# cpu1_gsm.net
KiCad netlist of a schematic drawn in Altium Designer
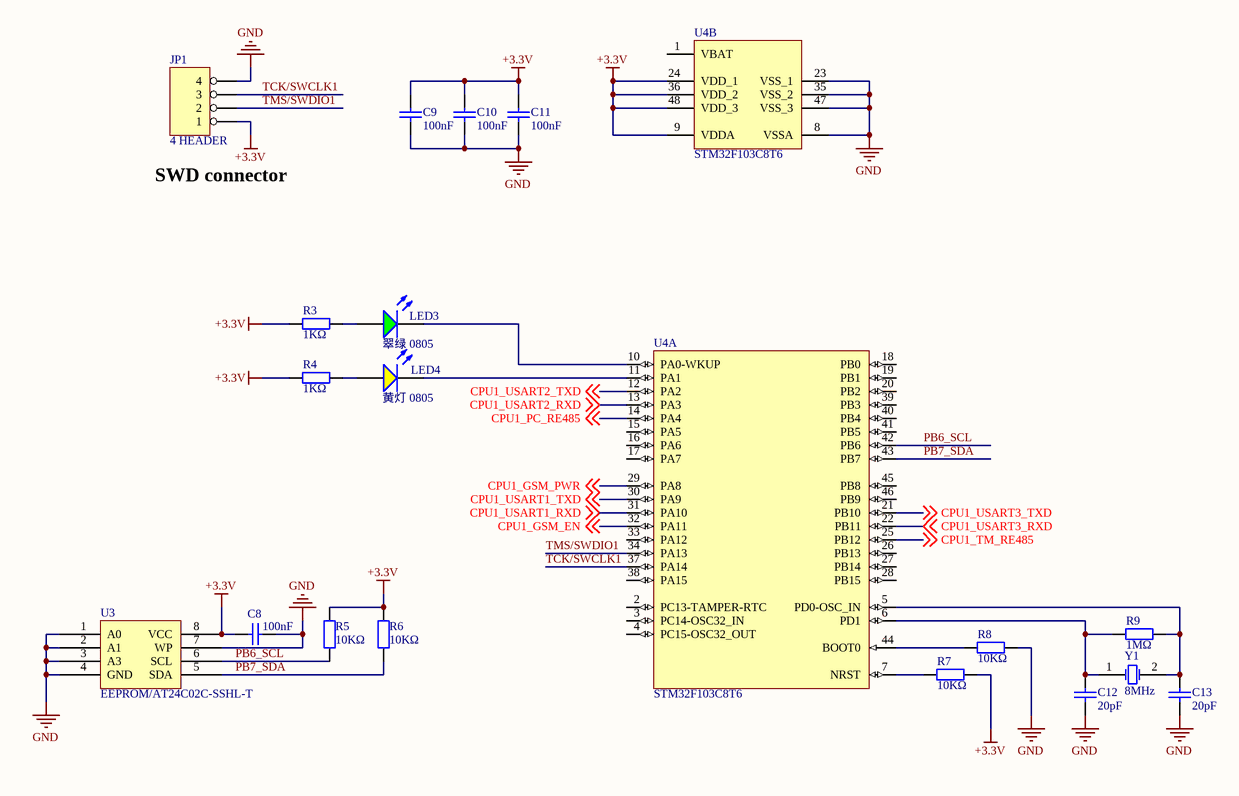
[diagram p0: cpu1_gsm.SchDoc]

(export (version "E")
  (design (tool "Eeschema 10.0.6"))
  (components
    (comp (ref "C8")
      (value "100nF")
      (footprint "0805_C")
      (description "贴片电容")
      (libsource (lib "Miscellaneous Devices LC") (part "0805 100nF(104) 10% 50V"))
    )
    (comp (ref "C9")
      (value "100nF")
      (footprint "0805_C")
      (description "贴片电容")
      (libsource (lib "Miscellaneous Devices LC") (part "0805 100nF(104) 10% 50V"))
    )
    (comp (ref "C10")
      (value "100nF")
      (footprint "0805_C")
      (description "贴片电容")
      (libsource (lib "Miscellaneous Devices LC") (part "0805 100nF(104) 10% 50V"))
    )
    (comp (ref "C11")
      (value "100nF")
      (footprint "0805_C")
      (description "贴片电容")
      (libsource (lib "Miscellaneous Devices LC") (part "0805 100nF(104) 10% 50V"))
    )
    (comp (ref "C12")
      (value "20pF")
      (footprint "0805_C")
      (description "贴片电容")
      (libsource (lib "Miscellaneous Devices LC") (part "0805 100nF(104) 10% 50V"))
    )
    (comp (ref "C13")
      (value "20pF")
      (footprint "0805_C")
      (description "贴片电容")
      (libsource (lib "Miscellaneous Devices LC") (part "0805 100nF(104) 10% 50V"))
    )
    (comp (ref "JP1")
      (value "4 HEADER")
      (footprint "CON4_1.5")
      (description "4 Pin Header")
      (libsource (lib "Miscellaneous Devices") (part "4 HEADER"))
    )
    (comp (ref "LED3")
      (value "翠绿 0805")
      (footprint "0805_LED_S1")
      (description "发光二极管")
      (libsource (lib "Miscellaneous Devices LC") (part "0805 翠绿"))
    )
    (comp (ref "LED4")
      (value "黄灯 0805")
      (footprint "0805_LED_S1")
      (description "发光二极管")
      (libsource (lib "Miscellaneous Devices LC") (part "0805 黄灯"))
    )
    (comp (ref "R3")
      (value "1KΩ")
      (footprint "0805_R")
      (description "贴片电阻")
      (libsource (lib "") (part "0805 11KΩ (1102) 1%_1"))
    )
    (comp (ref "R4")
      (value "1KΩ")
      (footprint "0805_R")
      (description "贴片电阻")
      (libsource (lib "") (part "0805 11KΩ (1102) 1%_1"))
    )
    (comp (ref "R5")
      (value "10KΩ")
      (footprint "0805_R")
      (description "贴片电阻")
      (libsource (lib "") (part "0805 11KΩ (1102) 1%_2"))
    )
    (comp (ref "R6")
      (value "10KΩ")
      (footprint "0805_R")
      (description "贴片电阻")
      (libsource (lib "") (part "0805 11KΩ (1102) 1%_2"))
    )
    (comp (ref "R7")
      (value "10KΩ")
      (footprint "0805_R")
      (description "贴片电阻")
      (libsource (lib "Miscellaneous Devices LC") (part "0805 11KΩ (1102) 1%"))
    )
    (comp (ref "R8")
      (value "10KΩ")
      (footprint "0805_R")
      (description "贴片电阻")
      (libsource (lib "Miscellaneous Devices LC") (part "0805 11KΩ (1102) 1%"))
    )
    (comp (ref "R9")
      (value "1MΩ")
      (footprint "0805_R")
      (description "贴片电阻")
      (libsource (lib "Miscellaneous Devices LC") (part "0805 11KΩ (1102) 1%"))
    )
    (comp (ref "U3")
      (value "EEPROM/AT24C02C-SSHL-T")
      (footprint "SOIC-8_150mil")
      (description "EEPROM")
      (libsource (lib "Miscellaneous Devices LC") (part "EEPROM/AT24C256C-SSHL-T"))
    )
    (comp (ref "U4")
      (value "STM32F103C8T6")
      (footprint "LQFP-48_7x7x05P")
      (description "ARM")
      (libsource (lib "Miscellaneous Devices LC") (part "STM32F103C8T6"))
    )
    (comp (ref "Y1")
      (value "8MHz")
      (footprint "XTAL_US1")
      (description "Crystal Oscillator")
      (fields (field (name "PUBLISHER") "Altium Limited"))
      (libsource (lib "战舰STM32开发板底板封装库") (part "XTAL"))
    )
  )
  (nets
    (net (code "1") (name "+3.3V") (class "Default")
      (node (ref "C10") (pin "2") (pinfunction "2_2") (pintype "passive"))
      (node (ref "C11") (pin "2") (pinfunction "2_2") (pintype "passive"))
      (node (ref "C8") (pin "2") (pinfunction "2_2") (pintype "passive"))
      (node (ref "C9") (pin "2") (pinfunction "2_2") (pintype "passive"))
      (node (ref "JP1") (pin "1") (pinfunction "1_1") (pintype "passive"))
      (node (ref "R3") (pin "1") (pinfunction "1_1") (pintype "passive"))
      (node (ref "R4") (pin "1") (pinfunction "1_1") (pintype "passive"))
      (node (ref "R5") (pin "1") (pinfunction "1_1") (pintype "passive"))
      (node (ref "R6") (pin "1") (pinfunction "1_1") (pintype "passive"))
      (node (ref "R7") (pin "1") (pinfunction "1_1") (pintype "passive"))
      (node (ref "U3") (pin "8") (pinfunction "VCC_8") (pintype "passive"))
      (node (ref "U4") (pin "24") (pinfunction "VDD_1_24") (pintype "power_in"))
      (node (ref "U4") (pin "36") (pinfunction "VDD_2_36") (pintype "power_in"))
      (node (ref "U4") (pin "48") (pinfunction "VDD_3_48") (pintype "power_in"))
      (node (ref "U4") (pin "9") (pinfunction "VDDA_9") (pintype "power_in"))
    )
    (net (code "2") (name "/PB6_SCL") (class "Default")
      (node (ref "R5") (pin "2") (pinfunction "2_2") (pintype "passive"))
      (node (ref "U3") (pin "6") (pinfunction "SCL_6") (pintype "passive"))
      (node (ref "U4") (pin "42") (pinfunction "PB6_42") (pintype "bidirectional"))
    )
    (net (code "3") (name "/PB7_SDA") (class "Default")
      (node (ref "R6") (pin "2") (pinfunction "2_2") (pintype "passive"))
      (node (ref "U3") (pin "5") (pinfunction "SDA_5") (pintype "passive"))
      (node (ref "U4") (pin "43") (pinfunction "PB7_43") (pintype "bidirectional"))
    )
    (net (code "4") (name "/TCK{slash}SWCLK1") (class "Default")
      (node (ref "JP1") (pin "3") (pinfunction "3_3") (pintype "passive"))
      (node (ref "U4") (pin "37") (pinfunction "PA14_37") (pintype "bidirectional"))
    )
    (net (code "5") (name "/TMS{slash}SWDIO1") (class "Default")
      (node (ref "JP1") (pin "2") (pinfunction "2_2") (pintype "passive"))
      (node (ref "U4") (pin "34") (pinfunction "PA13_34") (pintype "bidirectional"))
    )
    (net (code "6") (name "CPU1_GSM_EN") (class "Default")
      (node (ref "U4") (pin "32") (pinfunction "PA11_32") (pintype "bidirectional"))
    )
    (net (code "7") (name "CPU1_GSM_PWR") (class "Default")
      (node (ref "U4") (pin "29") (pinfunction "PA8_29") (pintype "bidirectional"))
    )
    (net (code "8") (name "CPU1_PC_RE485") (class "Default")
      (node (ref "U4") (pin "14") (pinfunction "PA4_14") (pintype "bidirectional"))
    )
    (net (code "9") (name "CPU1_TM_RE485") (class "Default")
      (node (ref "U4") (pin "25") (pinfunction "PB12_25") (pintype "bidirectional"))
    )
    (net (code "10") (name "CPU1_USART1_RXD") (class "Default")
      (node (ref "U4") (pin "31") (pinfunction "PA10_31") (pintype "bidirectional"))
    )
    (net (code "11") (name "CPU1_USART1_TXD") (class "Default")
      (node (ref "U4") (pin "30") (pinfunction "PA9_30") (pintype "bidirectional"))
    )
    (net (code "12") (name "CPU1_USART2_RXD") (class "Default")
      (node (ref "U4") (pin "13") (pinfunction "PA3_13") (pintype "bidirectional"))
    )
    (net (code "13") (name "CPU1_USART2_TXD") (class "Default")
      (node (ref "U4") (pin "12") (pinfunction "PA2_12") (pintype "bidirectional"))
    )
    (net (code "14") (name "CPU1_USART3_RXD") (class "Default")
      (node (ref "U4") (pin "22") (pinfunction "PB11_22") (pintype "bidirectional"))
    )
    (net (code "15") (name "CPU1_USART3_TXD") (class "Default")
      (node (ref "U4") (pin "21") (pinfunction "PB10_21") (pintype "bidirectional"))
    )
    (net (code "16") (name "GND") (class "Default")
      (node (ref "C10") (pin "1") (pinfunction "1_1") (pintype "passive"))
      (node (ref "C11") (pin "1") (pinfunction "1_1") (pintype "passive"))
      (node (ref "C12") (pin "1") (pinfunction "1_1") (pintype "passive"))
      (node (ref "C13") (pin "1") (pinfunction "1_1") (pintype "passive"))
      (node (ref "C8") (pin "1") (pinfunction "1_1") (pintype "passive"))
      (node (ref "C9") (pin "1") (pinfunction "1_1") (pintype "passive"))
      (node (ref "JP1") (pin "4") (pinfunction "4_4") (pintype "passive"))
      (node (ref "R8") (pin "1") (pinfunction "1_1") (pintype "passive"))
      (node (ref "U3") (pin "1") (pinfunction "A0_1") (pintype "passive"))
      (node (ref "U3") (pin "2") (pinfunction "A1_2") (pintype "passive"))
      (node (ref "U3") (pin "3") (pinfunction "A3_3") (pintype "passive"))
      (node (ref "U3") (pin "4") (pinfunction "GND_4") (pintype "passive"))
      (node (ref "U3") (pin "7") (pinfunction "WP_7") (pintype "passive"))
      (node (ref "U4") (pin "23") (pinfunction "VSS_1_23") (pintype "power_in"))
      (node (ref "U4") (pin "35") (pinfunction "VSS_2_35") (pintype "power_in"))
      (node (ref "U4") (pin "47") (pinfunction "VSS_3_47") (pintype "power_in"))
      (node (ref "U4") (pin "8") (pinfunction "VSSA_8") (pintype "power_in"))
    )
    (net (code "17") (name "Net-(LED3-PadA)") (class "Default")
      (node (ref "LED3") (pin "A") (pinfunction "A_A") (pintype "passive"))
      (node (ref "R3") (pin "2") (pinfunction "2_2") (pintype "passive"))
    )
    (net (code "18") (name "Net-(LED4-PadA)") (class "Default")
      (node (ref "LED4") (pin "A") (pinfunction "A_A") (pintype "passive"))
      (node (ref "R4") (pin "2") (pinfunction "2_2") (pintype "passive"))
    )
    (net (code "19") (name "Net-(U4A-BOOT0)") (class "Default")
      (node (ref "R8") (pin "2") (pinfunction "2_2") (pintype "passive"))
      (node (ref "U4") (pin "44") (pinfunction "BOOT0_44") (pintype "input"))
    )
    (net (code "20") (name "Net-(U4A-NRST)") (class "Default")
      (node (ref "R7") (pin "2") (pinfunction "2_2") (pintype "passive"))
      (node (ref "U4") (pin "7") (pinfunction "NRST_7") (pintype "bidirectional"))
    )
    (net (code "21") (name "Net-(U4A-PA0-WKUP)") (class "Default")
      (node (ref "LED3") (pin "K") (pinfunction "K_K") (pintype "passive"))
      (node (ref "U4") (pin "10") (pinfunction "PA0-WKUP_10") (pintype "bidirectional"))
    )
    (net (code "22") (name "Net-(U4A-PA1)") (class "Default")
      (node (ref "LED4") (pin "K") (pinfunction "K_K") (pintype "passive"))
      (node (ref "U4") (pin "11") (pinfunction "PA1_11") (pintype "bidirectional"))
    )
    (net (code "23") (name "Net-(U4A-PD0-OSC_IN)") (class "Default")
      (node (ref "C13") (pin "2") (pinfunction "2_2") (pintype "passive"))
      (node (ref "R9") (pin "1") (pinfunction "1_1") (pintype "passive"))
      (node (ref "U4") (pin "5") (pinfunction "PD0-OSC_IN_5") (pintype "bidirectional"))
      (node (ref "Y1") (pin "2") (pinfunction "OSC2_2") (pintype "passive"))
    )
    (net (code "24") (name "Net-(U4A-PD1)") (class "Default")
      (node (ref "C12") (pin "2") (pinfunction "2_2") (pintype "passive"))
      (node (ref "R9") (pin "2") (pinfunction "2_2") (pintype "passive"))
      (node (ref "U4") (pin "6") (pinfunction "PD1_6") (pintype "bidirectional"))
      (node (ref "Y1") (pin "1") (pinfunction "OSC1_1") (pintype "passive"))
    )
    (net (code "25") (name "unconnected-(U4A-PA5-Pad15)") (class "Default")
      (node (ref "U4") (pin "15") (pinfunction "PA5_15") (pintype "bidirectional"))
    )
    (net (code "26") (name "unconnected-(U4A-PA6-Pad16)") (class "Default")
      (node (ref "U4") (pin "16") (pinfunction "PA6_16") (pintype "bidirectional"))
    )
    (net (code "27") (name "unconnected-(U4A-PA7-Pad17)") (class "Default")
      (node (ref "U4") (pin "17") (pinfunction "PA7_17") (pintype "bidirectional"))
    )
    (net (code "28") (name "unconnected-(U4A-PA12-Pad33)") (class "Default")
      (node (ref "U4") (pin "33") (pinfunction "PA12_33") (pintype "bidirectional"))
    )
    (net (code "29") (name "unconnected-(U4A-PA15-Pad38)") (class "Default")
      (node (ref "U4") (pin "38") (pinfunction "PA15_38") (pintype "bidirectional"))
    )
    (net (code "30") (name "unconnected-(U4A-PB0-Pad18)") (class "Default")
      (node (ref "U4") (pin "18") (pinfunction "PB0_18") (pintype "bidirectional"))
    )
    (net (code "31") (name "unconnected-(U4A-PB1-Pad19)") (class "Default")
      (node (ref "U4") (pin "19") (pinfunction "PB1_19") (pintype "bidirectional"))
    )
    (net (code "32") (name "unconnected-(U4A-PB2-Pad20)") (class "Default")
      (node (ref "U4") (pin "20") (pinfunction "PB2_20") (pintype "bidirectional"))
    )
    (net (code "33") (name "unconnected-(U4A-PB3-Pad39)") (class "Default")
      (node (ref "U4") (pin "39") (pinfunction "PB3_39") (pintype "bidirectional"))
    )
    (net (code "34") (name "unconnected-(U4A-PB4-Pad40)") (class "Default")
      (node (ref "U4") (pin "40") (pinfunction "PB4_40") (pintype "bidirectional"))
    )
    (net (code "35") (name "unconnected-(U4A-PB5-Pad41)") (class "Default")
      (node (ref "U4") (pin "41") (pinfunction "PB5_41") (pintype "bidirectional"))
    )
    (net (code "36") (name "unconnected-(U4A-PB8-Pad45)") (class "Default")
      (node (ref "U4") (pin "45") (pinfunction "PB8_45") (pintype "bidirectional"))
    )
    (net (code "37") (name "unconnected-(U4A-PB9-Pad46)") (class "Default")
      (node (ref "U4") (pin "46") (pinfunction "PB9_46") (pintype "bidirectional"))
    )
    (net (code "38") (name "unconnected-(U4A-PB13-Pad26)") (class "Default")
      (node (ref "U4") (pin "26") (pinfunction "PB13_26") (pintype "bidirectional"))
    )
    (net (code "39") (name "unconnected-(U4A-PB14-Pad27)") (class "Default")
      (node (ref "U4") (pin "27") (pinfunction "PB14_27") (pintype "bidirectional"))
    )
    (net (code "40") (name "unconnected-(U4A-PB15-Pad28)") (class "Default")
      (node (ref "U4") (pin "28") (pinfunction "PB15_28") (pintype "bidirectional"))
    )
    (net (code "41") (name "unconnected-(U4A-PC13-TAMPER-RTC-Pad2)") (class "Default")
      (node (ref "U4") (pin "2") (pinfunction "PC13-TAMPER-RTC_2") (pintype "bidirectional"))
    )
    (net (code "42") (name "unconnected-(U4A-PC14-OSC32_IN-Pad3)") (class "Default")
      (node (ref "U4") (pin "3") (pinfunction "PC14-OSC32_IN_3") (pintype "bidirectional"))
    )
    (net (code "43") (name "unconnected-(U4A-PC15-OSC32_OUT-Pad4)") (class "Default")
      (node (ref "U4") (pin "4") (pinfunction "PC15-OSC32_OUT_4") (pintype "bidirectional"))
    )
    (net (code "44") (name "unconnected-(U4B-VBAT-Pad1)") (class "Default")
      (node (ref "U4") (pin "1") (pinfunction "VBAT_1") (pintype "power_in"))
    )
  )
)
